# Sch_mas_suiveur_ligne.net
KiCad netlist of a schematic drawn in Altium Designer
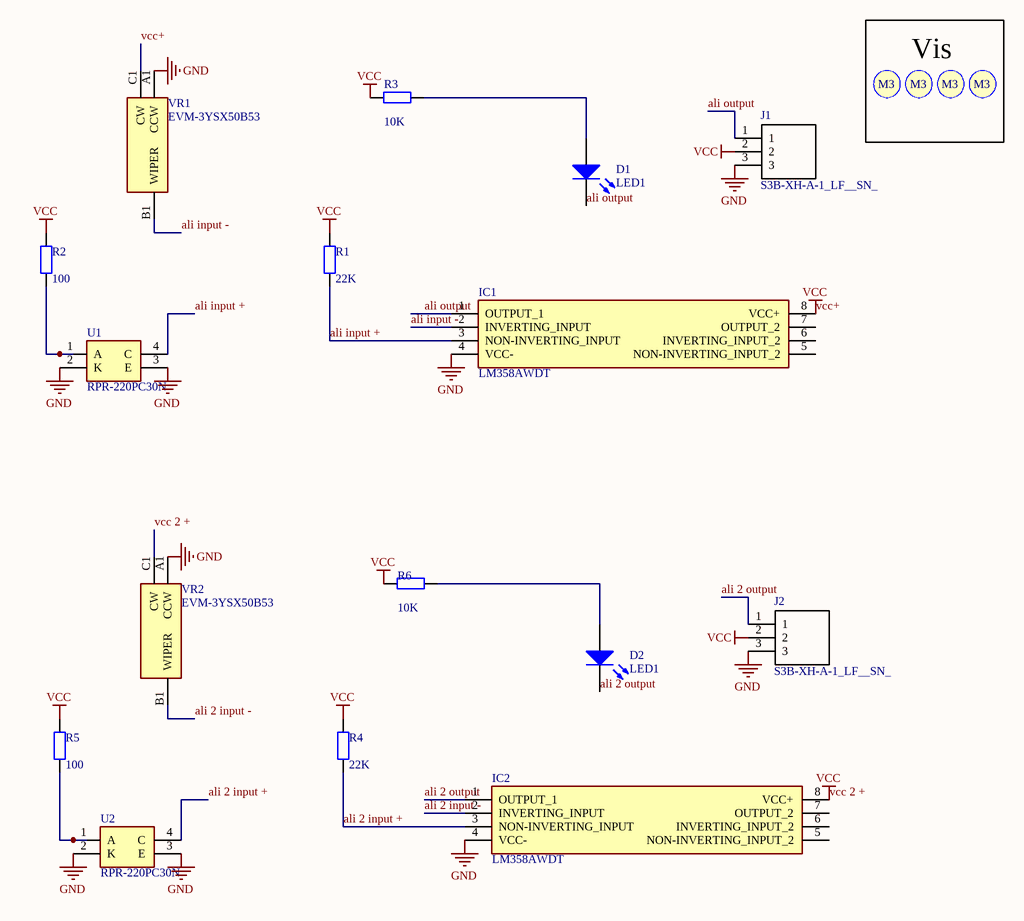
[diagram p0: Schémas suiveur ligne.SchDoc]

(export (version "E")
  (design (tool "Eeschema 10.0.6"))
  (components
    (comp (ref "D1")
      (value "LED1")
      (footprint "KP-3216SEC")
      (description "Typical RED GaAs LED")
      (fields (field (name "PUBLISHER") "Altium Limited"))
      (libsource (lib "Miscellaneous Devices") (part "LED1"))
    )
    (comp (ref "D2")
      (value "LED1")
      (footprint "KP-3216SEC")
      (description "Typical RED GaAs LED")
      (fields (field (name "PUBLISHER") "Altium Limited"))
      (libsource (lib "Miscellaneous Devices") (part "LED1"))
    )
    (comp (ref "IC1")
      (value "LM358AWDT")
      (footprint "SOIC127P600X175-8N")
      (description "Integrated Circuit")
      (fields (field (name "MOUSER PART NUMBER") "511-LM358AWDT"))
      (libsource (lib "*") (part "LM358AWDT"))
    )
    (comp (ref "IC2")
      (value "LM358AWDT")
      (footprint "SOIC127P600X175-8N")
      (description "Integrated Circuit")
      (fields (field (name "MOUSER PART NUMBER") "511-LM358AWDT"))
      (libsource (lib "*") (part "LM358AWDT"))
    )
    (comp (ref "J1")
      (value "S3B-XH-A-1_LF__SN_")
      (footprint "S3B-XH-A")
      (description "Connector")
      (fields (field (name "MANUFACTURER_PART_NUMBER") "S3B-XH-A-1(LF)(SN)"))
      (libsource (lib "SamacSys") (part "S3B-XH-A-1_LF__SN_"))
    )
    (comp (ref "J2")
      (value "S3B-XH-A-1_LF__SN_")
      (footprint "S3B-XH-A")
      (description "Connector")
      (fields (field (name "MANUFACTURER_PART_NUMBER") "S3B-XH-A-1(LF)(SN)"))
      (libsource (lib "SamacSys") (part "S3B-XH-A-1_LF__SN_"))
    )
    (comp (ref "R1")
      (value "22K")
      (footprint "Resistor 1206")
      (description "Resistor")
      (fields (field (name "PUBLISHER") "Altium Limited"))
      (libsource (lib "Miscellaneous Devices") (part "Res2"))
    )
    (comp (ref "R2")
      (value "100")
      (footprint "Resistor 1206")
      (description "Resistor")
      (fields (field (name "PUBLISHER") "Altium Limited"))
      (libsource (lib "Miscellaneous Devices") (part "Res2"))
    )
    (comp (ref "R3")
      (value "10K")
      (footprint "Resistor 1206")
      (description "Resistor")
      (fields (field (name "PUBLISHER") "Altium Limited"))
      (libsource (lib "") (part "Res2_1"))
    )
    (comp (ref "R4")
      (value "22K")
      (footprint "Resistor 1206")
      (description "Resistor")
      (fields (field (name "PUBLISHER") "Altium Limited"))
      (libsource (lib "Miscellaneous Devices") (part "Res2"))
    )
    (comp (ref "R5")
      (value "100")
      (footprint "Resistor 1206")
      (description "Resistor")
      (fields (field (name "PUBLISHER") "Altium Limited"))
      (libsource (lib "Miscellaneous Devices") (part "Res2"))
    )
    (comp (ref "R6")
      (value "10K")
      (footprint "Resistor 1206")
      (description "Resistor")
      (fields (field (name "PUBLISHER") "Altium Limited"))
      (libsource (lib "") (part "Res2_1"))
    )
    (comp (ref "S1")
      (value "Screw M3")
      (footprint "Screw M3")
      (libsource (lib "Robot_2019") (part "Screw M3"))
    )
    (comp (ref "S2")
      (value "Screw M3")
      (footprint "Screw M3")
      (libsource (lib "Robot_2019") (part "Screw M3"))
    )
    (comp (ref "S3")
      (value "Screw M3")
      (footprint "Screw M3")
      (libsource (lib "Robot_2019") (part "Screw M3"))
    )
    (comp (ref "S4")
      (value "Screw M3")
      (footprint "Screw M3")
      (libsource (lib "Robot_2019") (part "Screw M3"))
    )
    (comp (ref "U1")
      (value "RPR-220PC30N")
      (footprint "RPR220PC30N")
      (description "Undefined or Miscellaneous")
      (fields (field (name "MOUSER PART NUMBER") "755-RPR-220PC30N"))
      (libsource (lib "SamacSys") (part "RPR-220PC30N"))
    )
    (comp (ref "U2")
      (value "RPR-220PC30N")
      (footprint "RPR220PC30N")
      (description "Undefined or Miscellaneous")
      (fields (field (name "MOUSER PART NUMBER") "755-RPR-220PC30N"))
      (libsource (lib "SamacSys") (part "RPR-220PC30N"))
    )
    (comp (ref "VR1")
      (value "EVM-3YSX50B53")
      (footprint "EVM3YSX50B53")
      (description "Variable Resistor")
      (fields (field (name "MOUSER PART NUMBER") "667-EVM-3YSX50B53"))
      (libsource (lib "*") (part "EVM-3YSX50B53"))
    )
    (comp (ref "VR2")
      (value "EVM-3YSX50B53")
      (footprint "EVM3YSX50B53")
      (description "Variable Resistor")
      (fields (field (name "MOUSER PART NUMBER") "667-EVM-3YSX50B53"))
      (libsource (lib "*") (part "EVM-3YSX50B53"))
    )
  )
  (nets
    (net (code "1") (name "/ali 2 input +") (class "Default")
      (node (ref "IC2") (pin "3") (pinfunction "NON-INVERTING_INPUT_3") (pintype "passive"))
      (node (ref "R4") (pin "1") (pinfunction "1_1") (pintype "passive"))
      (node (ref "U2") (pin "4") (pinfunction "C_4") (pintype "passive"))
    )
    (net (code "2") (name "/ali 2 input -") (class "Default")
      (node (ref "IC2") (pin "2") (pinfunction "INVERTING_INPUT_2") (pintype "passive"))
      (node (ref "VR2") (pin "B1") (pinfunction "WIPER_B1") (pintype "passive"))
    )
    (net (code "3") (name "/ali 2 output") (class "Default")
      (node (ref "D2") (pin "2") (pinfunction "K_2") (pintype "passive"))
      (node (ref "IC2") (pin "1") (pinfunction "OUTPUT_1_1") (pintype "passive"))
      (node (ref "J2") (pin "1") (pinfunction "1_1") (pintype "passive"))
    )
    (net (code "4") (name "/ali input +") (class "Default")
      (node (ref "IC1") (pin "3") (pinfunction "NON-INVERTING_INPUT_3") (pintype "passive"))
      (node (ref "R1") (pin "1") (pinfunction "1_1") (pintype "passive"))
      (node (ref "U1") (pin "4") (pinfunction "C_4") (pintype "passive"))
    )
    (net (code "5") (name "/ali input -") (class "Default")
      (node (ref "IC1") (pin "2") (pinfunction "INVERTING_INPUT_2") (pintype "passive"))
      (node (ref "VR1") (pin "B1") (pinfunction "WIPER_B1") (pintype "passive"))
    )
    (net (code "6") (name "/ali output") (class "Default")
      (node (ref "D1") (pin "2") (pinfunction "K_2") (pintype "passive"))
      (node (ref "IC1") (pin "1") (pinfunction "OUTPUT_1_1") (pintype "passive"))
      (node (ref "J1") (pin "1") (pinfunction "1_1") (pintype "passive"))
    )
    (net (code "7") (name "GND") (class "Default")
      (node (ref "IC1") (pin "4") (pinfunction "VCC-_4") (pintype "passive"))
      (node (ref "IC2") (pin "4") (pinfunction "VCC-_4") (pintype "passive"))
      (node (ref "J1") (pin "3") (pinfunction "3_3") (pintype "passive"))
      (node (ref "J2") (pin "3") (pinfunction "3_3") (pintype "passive"))
      (node (ref "U1") (pin "2") (pinfunction "K_2") (pintype "passive"))
      (node (ref "U1") (pin "3") (pinfunction "E_3") (pintype "passive"))
      (node (ref "U2") (pin "2") (pinfunction "K_2") (pintype "passive"))
      (node (ref "U2") (pin "3") (pinfunction "E_3") (pintype "passive"))
      (node (ref "VR1") (pin "A1") (pinfunction "CCW_A1") (pintype "passive"))
      (node (ref "VR2") (pin "A1") (pinfunction "CCW_A1") (pintype "passive"))
    )
    (net (code "8") (name "Net-(D1-A)") (class "Default")
      (node (ref "D1") (pin "1") (pinfunction "A_1") (pintype "passive"))
      (node (ref "R3") (pin "1") (pinfunction "1_1") (pintype "passive"))
    )
    (net (code "9") (name "Net-(D2-A)") (class "Default")
      (node (ref "D2") (pin "1") (pinfunction "A_1") (pintype "passive"))
      (node (ref "R6") (pin "1") (pinfunction "1_1") (pintype "passive"))
    )
    (net (code "10") (name "Net-(U1-A)") (class "Default")
      (node (ref "R2") (pin "1") (pinfunction "1_1") (pintype "passive"))
      (node (ref "U1") (pin "1") (pinfunction "A_1") (pintype "passive"))
    )
    (net (code "11") (name "Net-(U2-A)") (class "Default")
      (node (ref "R5") (pin "1") (pinfunction "1_1") (pintype "passive"))
      (node (ref "U2") (pin "1") (pinfunction "A_1") (pintype "passive"))
    )
    (net (code "12") (name "VCC") (class "Default")
      (node (ref "IC1") (pin "8") (pinfunction "VCC+_8") (pintype "passive"))
      (node (ref "IC2") (pin "8") (pinfunction "VCC+_8") (pintype "passive"))
      (node (ref "J1") (pin "2") (pinfunction "2_2") (pintype "passive"))
      (node (ref "J2") (pin "2") (pinfunction "2_2") (pintype "passive"))
      (node (ref "R1") (pin "2") (pinfunction "2_2") (pintype "passive"))
      (node (ref "R2") (pin "2") (pinfunction "2_2") (pintype "passive"))
      (node (ref "R3") (pin "2") (pinfunction "2_2") (pintype "passive"))
      (node (ref "R4") (pin "2") (pinfunction "2_2") (pintype "passive"))
      (node (ref "R5") (pin "2") (pinfunction "2_2") (pintype "passive"))
      (node (ref "R6") (pin "2") (pinfunction "2_2") (pintype "passive"))
      (node (ref "VR1") (pin "C1") (pinfunction "CW_C1") (pintype "passive"))
      (node (ref "VR2") (pin "C1") (pinfunction "CW_C1") (pintype "passive"))
    )
    (net (code "13") (name "unconnected-(IC1-INVERTING_INPUT_2-Pad6)") (class "Default")
      (node (ref "IC1") (pin "6") (pinfunction "INVERTING_INPUT_2_6") (pintype "passive"))
    )
    (net (code "14") (name "unconnected-(IC1-NON-INVERTING_INPUT_2-Pad5)") (class "Default")
      (node (ref "IC1") (pin "5") (pinfunction "NON-INVERTING_INPUT_2_5") (pintype "passive"))
    )
    (net (code "15") (name "unconnected-(IC1-OUTPUT_2-Pad7)") (class "Default")
      (node (ref "IC1") (pin "7") (pinfunction "OUTPUT_2_7") (pintype "passive"))
    )
    (net (code "16") (name "unconnected-(IC2-INVERTING_INPUT_2-Pad6)") (class "Default")
      (node (ref "IC2") (pin "6") (pinfunction "INVERTING_INPUT_2_6") (pintype "passive"))
    )
    (net (code "17") (name "unconnected-(IC2-NON-INVERTING_INPUT_2-Pad5)") (class "Default")
      (node (ref "IC2") (pin "5") (pinfunction "NON-INVERTING_INPUT_2_5") (pintype "passive"))
    )
    (net (code "18") (name "unconnected-(IC2-OUTPUT_2-Pad7)") (class "Default")
      (node (ref "IC2") (pin "7") (pinfunction "OUTPUT_2_7") (pintype "passive"))
    )
  )
)
